# power_bus_v1.net
KiCad netlist of a schematic drawn in EAGLE
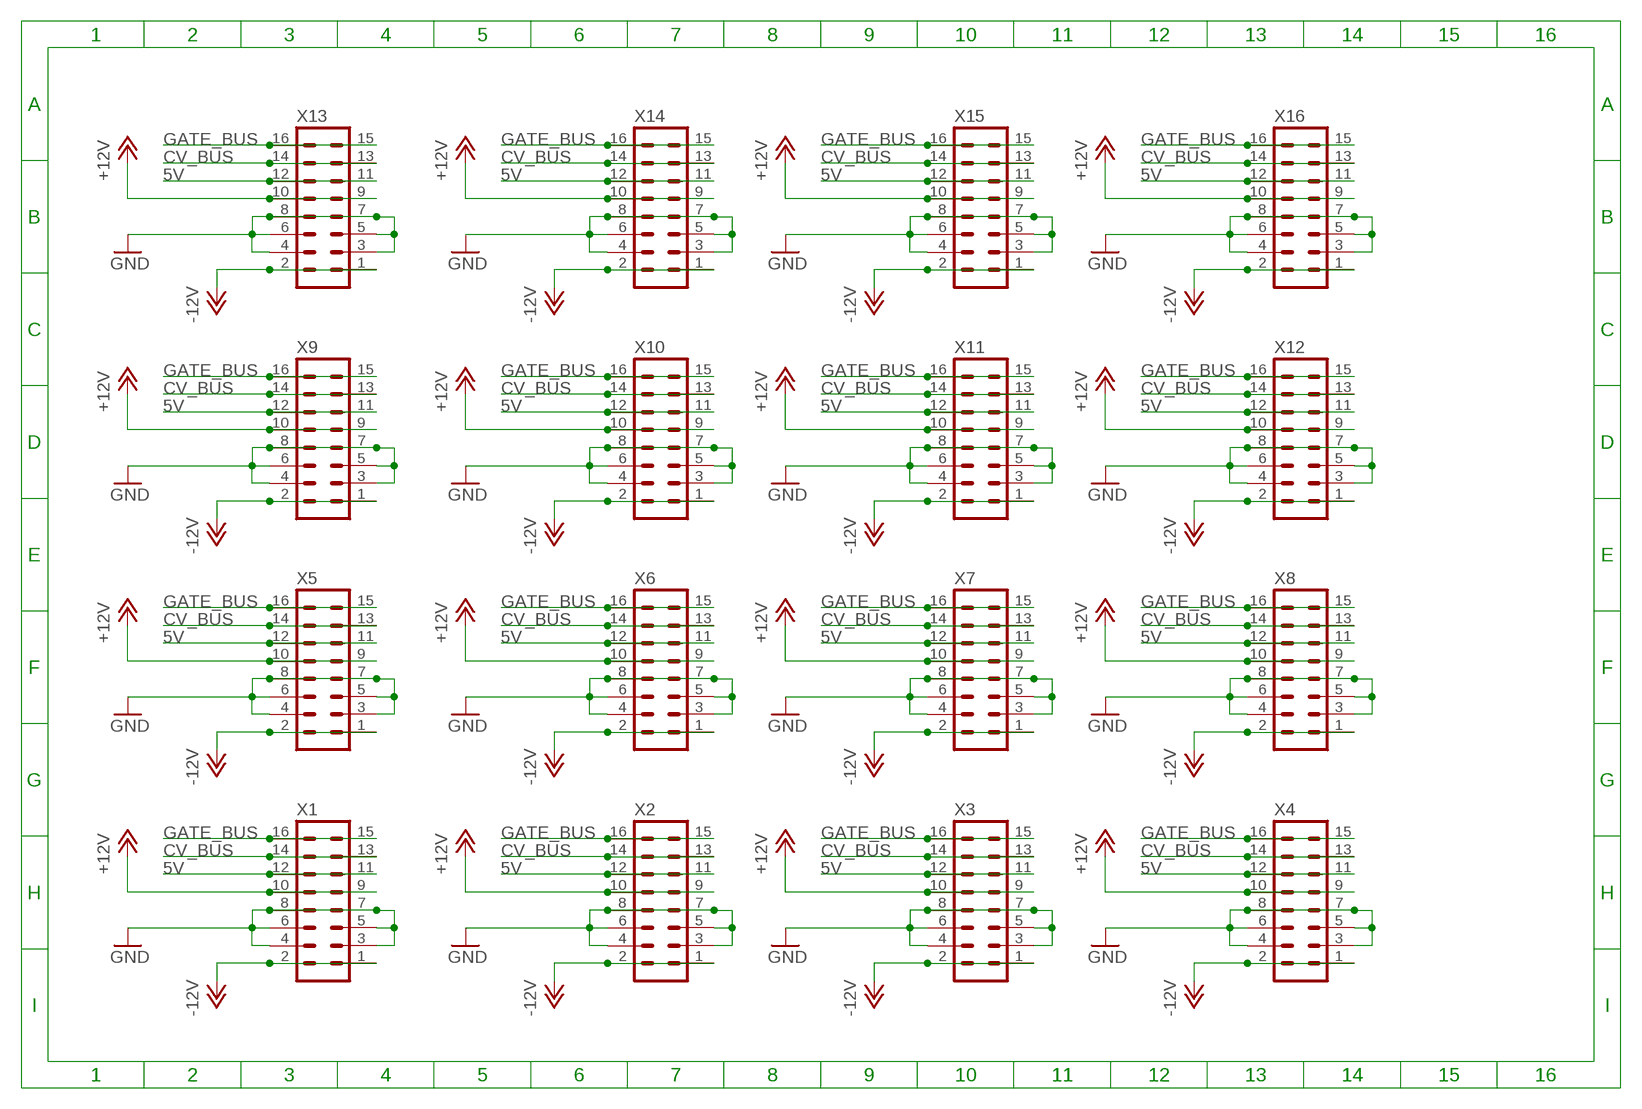
[diagram p0: schematic, sheet 1]

(export (version "E")
  (design (tool "Eeschema 10.0.6"))
  (components
    (comp (ref "X1")
      (value "ML16")
      (footprint "eagle-import:ML16")
      (libsource (lib "eagle-import") (part "ML16"))
    )
    (comp (ref "X2")
      (value "ML16")
      (footprint "eagle-import:ML16")
      (libsource (lib "eagle-import") (part "ML16"))
    )
    (comp (ref "X3")
      (value "ML16")
      (footprint "eagle-import:ML16")
      (libsource (lib "eagle-import") (part "ML16"))
    )
    (comp (ref "X4")
      (value "ML16")
      (footprint "eagle-import:ML16")
      (libsource (lib "eagle-import") (part "ML16"))
    )
    (comp (ref "X5")
      (value "ML16")
      (footprint "eagle-import:ML16")
      (libsource (lib "eagle-import") (part "ML16"))
    )
    (comp (ref "X6")
      (value "ML16")
      (footprint "eagle-import:ML16")
      (libsource (lib "eagle-import") (part "ML16"))
    )
    (comp (ref "X7")
      (value "ML16")
      (footprint "eagle-import:ML16")
      (libsource (lib "eagle-import") (part "ML16"))
    )
    (comp (ref "X8")
      (value "ML16")
      (footprint "eagle-import:ML16")
      (libsource (lib "eagle-import") (part "ML16"))
    )
    (comp (ref "X9")
      (value "ML16")
      (footprint "eagle-import:ML16")
      (libsource (lib "eagle-import") (part "ML16"))
    )
    (comp (ref "X10")
      (value "ML16")
      (footprint "eagle-import:ML16")
      (libsource (lib "eagle-import") (part "ML16"))
    )
    (comp (ref "X11")
      (value "ML16")
      (footprint "eagle-import:ML16")
      (libsource (lib "eagle-import") (part "ML16"))
    )
    (comp (ref "X12")
      (value "ML16")
      (footprint "eagle-import:ML16")
      (libsource (lib "eagle-import") (part "ML16"))
    )
    (comp (ref "X13")
      (value "ML16")
      (footprint "eagle-import:ML16")
      (libsource (lib "eagle-import") (part "ML16"))
    )
    (comp (ref "X14")
      (value "ML16")
      (footprint "eagle-import:ML16")
      (libsource (lib "eagle-import") (part "ML16"))
    )
    (comp (ref "X15")
      (value "ML16")
      (footprint "eagle-import:ML16")
      (libsource (lib "eagle-import") (part "ML16"))
    )
    (comp (ref "X16")
      (value "ML16")
      (footprint "eagle-import:ML16")
      (libsource (lib "eagle-import") (part "ML16"))
    )
  )
  (nets
    (net (code "1") (name "+12V") (class "Default")
      (node (ref "X1") (pin "10") (pinfunction "10_10") (pintype "passive"))
      (node (ref "X1") (pin "9") (pinfunction "9_9") (pintype "passive"))
      (node (ref "X10") (pin "10") (pinfunction "10_10") (pintype "passive"))
      (node (ref "X10") (pin "9") (pinfunction "9_9") (pintype "passive"))
      (node (ref "X11") (pin "10") (pinfunction "10_10") (pintype "passive"))
      (node (ref "X11") (pin "9") (pinfunction "9_9") (pintype "passive"))
      (node (ref "X12") (pin "10") (pinfunction "10_10") (pintype "passive"))
      (node (ref "X12") (pin "9") (pinfunction "9_9") (pintype "passive"))
      (node (ref "X13") (pin "10") (pinfunction "10_10") (pintype "passive"))
      (node (ref "X13") (pin "9") (pinfunction "9_9") (pintype "passive"))
      (node (ref "X14") (pin "10") (pinfunction "10_10") (pintype "passive"))
      (node (ref "X14") (pin "9") (pinfunction "9_9") (pintype "passive"))
      (node (ref "X15") (pin "10") (pinfunction "10_10") (pintype "passive"))
      (node (ref "X15") (pin "9") (pinfunction "9_9") (pintype "passive"))
      (node (ref "X16") (pin "10") (pinfunction "10_10") (pintype "passive"))
      (node (ref "X16") (pin "9") (pinfunction "9_9") (pintype "passive"))
      (node (ref "X2") (pin "10") (pinfunction "10_10") (pintype "passive"))
      (node (ref "X2") (pin "9") (pinfunction "9_9") (pintype "passive"))
      (node (ref "X3") (pin "10") (pinfunction "10_10") (pintype "passive"))
      (node (ref "X3") (pin "9") (pinfunction "9_9") (pintype "passive"))
      (node (ref "X4") (pin "10") (pinfunction "10_10") (pintype "passive"))
      (node (ref "X4") (pin "9") (pinfunction "9_9") (pintype "passive"))
      (node (ref "X5") (pin "10") (pinfunction "10_10") (pintype "passive"))
      (node (ref "X5") (pin "9") (pinfunction "9_9") (pintype "passive"))
      (node (ref "X6") (pin "10") (pinfunction "10_10") (pintype "passive"))
      (node (ref "X6") (pin "9") (pinfunction "9_9") (pintype "passive"))
      (node (ref "X7") (pin "10") (pinfunction "10_10") (pintype "passive"))
      (node (ref "X7") (pin "9") (pinfunction "9_9") (pintype "passive"))
      (node (ref "X8") (pin "10") (pinfunction "10_10") (pintype "passive"))
      (node (ref "X8") (pin "9") (pinfunction "9_9") (pintype "passive"))
      (node (ref "X9") (pin "10") (pinfunction "10_10") (pintype "passive"))
      (node (ref "X9") (pin "9") (pinfunction "9_9") (pintype "passive"))
    )
    (net (code "2") (name "-12V") (class "Default")
      (node (ref "X1") (pin "1") (pinfunction "1_1") (pintype "passive"))
      (node (ref "X1") (pin "2") (pinfunction "2_2") (pintype "passive"))
      (node (ref "X10") (pin "1") (pinfunction "1_1") (pintype "passive"))
      (node (ref "X10") (pin "2") (pinfunction "2_2") (pintype "passive"))
      (node (ref "X11") (pin "1") (pinfunction "1_1") (pintype "passive"))
      (node (ref "X11") (pin "2") (pinfunction "2_2") (pintype "passive"))
      (node (ref "X12") (pin "1") (pinfunction "1_1") (pintype "passive"))
      (node (ref "X12") (pin "2") (pinfunction "2_2") (pintype "passive"))
      (node (ref "X13") (pin "1") (pinfunction "1_1") (pintype "passive"))
      (node (ref "X13") (pin "2") (pinfunction "2_2") (pintype "passive"))
      (node (ref "X14") (pin "1") (pinfunction "1_1") (pintype "passive"))
      (node (ref "X14") (pin "2") (pinfunction "2_2") (pintype "passive"))
      (node (ref "X15") (pin "1") (pinfunction "1_1") (pintype "passive"))
      (node (ref "X15") (pin "2") (pinfunction "2_2") (pintype "passive"))
      (node (ref "X16") (pin "1") (pinfunction "1_1") (pintype "passive"))
      (node (ref "X16") (pin "2") (pinfunction "2_2") (pintype "passive"))
      (node (ref "X2") (pin "1") (pinfunction "1_1") (pintype "passive"))
      (node (ref "X2") (pin "2") (pinfunction "2_2") (pintype "passive"))
      (node (ref "X3") (pin "1") (pinfunction "1_1") (pintype "passive"))
      (node (ref "X3") (pin "2") (pinfunction "2_2") (pintype "passive"))
      (node (ref "X4") (pin "1") (pinfunction "1_1") (pintype "passive"))
      (node (ref "X4") (pin "2") (pinfunction "2_2") (pintype "passive"))
      (node (ref "X5") (pin "1") (pinfunction "1_1") (pintype "passive"))
      (node (ref "X5") (pin "2") (pinfunction "2_2") (pintype "passive"))
      (node (ref "X6") (pin "1") (pinfunction "1_1") (pintype "passive"))
      (node (ref "X6") (pin "2") (pinfunction "2_2") (pintype "passive"))
      (node (ref "X7") (pin "1") (pinfunction "1_1") (pintype "passive"))
      (node (ref "X7") (pin "2") (pinfunction "2_2") (pintype "passive"))
      (node (ref "X8") (pin "1") (pinfunction "1_1") (pintype "passive"))
      (node (ref "X8") (pin "2") (pinfunction "2_2") (pintype "passive"))
      (node (ref "X9") (pin "1") (pinfunction "1_1") (pintype "passive"))
      (node (ref "X9") (pin "2") (pinfunction "2_2") (pintype "passive"))
    )
    (net (code "3") (name "/5V") (class "Default")
      (node (ref "X1") (pin "11") (pinfunction "11_11") (pintype "passive"))
      (node (ref "X1") (pin "12") (pinfunction "12_12") (pintype "passive"))
      (node (ref "X10") (pin "11") (pinfunction "11_11") (pintype "passive"))
      (node (ref "X10") (pin "12") (pinfunction "12_12") (pintype "passive"))
      (node (ref "X11") (pin "11") (pinfunction "11_11") (pintype "passive"))
      (node (ref "X11") (pin "12") (pinfunction "12_12") (pintype "passive"))
      (node (ref "X12") (pin "11") (pinfunction "11_11") (pintype "passive"))
      (node (ref "X12") (pin "12") (pinfunction "12_12") (pintype "passive"))
      (node (ref "X13") (pin "11") (pinfunction "11_11") (pintype "passive"))
      (node (ref "X13") (pin "12") (pinfunction "12_12") (pintype "passive"))
      (node (ref "X14") (pin "11") (pinfunction "11_11") (pintype "passive"))
      (node (ref "X14") (pin "12") (pinfunction "12_12") (pintype "passive"))
      (node (ref "X15") (pin "11") (pinfunction "11_11") (pintype "passive"))
      (node (ref "X15") (pin "12") (pinfunction "12_12") (pintype "passive"))
      (node (ref "X16") (pin "11") (pinfunction "11_11") (pintype "passive"))
      (node (ref "X16") (pin "12") (pinfunction "12_12") (pintype "passive"))
      (node (ref "X2") (pin "11") (pinfunction "11_11") (pintype "passive"))
      (node (ref "X2") (pin "12") (pinfunction "12_12") (pintype "passive"))
      (node (ref "X3") (pin "11") (pinfunction "11_11") (pintype "passive"))
      (node (ref "X3") (pin "12") (pinfunction "12_12") (pintype "passive"))
      (node (ref "X4") (pin "11") (pinfunction "11_11") (pintype "passive"))
      (node (ref "X4") (pin "12") (pinfunction "12_12") (pintype "passive"))
      (node (ref "X5") (pin "11") (pinfunction "11_11") (pintype "passive"))
      (node (ref "X5") (pin "12") (pinfunction "12_12") (pintype "passive"))
      (node (ref "X6") (pin "11") (pinfunction "11_11") (pintype "passive"))
      (node (ref "X6") (pin "12") (pinfunction "12_12") (pintype "passive"))
      (node (ref "X7") (pin "11") (pinfunction "11_11") (pintype "passive"))
      (node (ref "X7") (pin "12") (pinfunction "12_12") (pintype "passive"))
      (node (ref "X8") (pin "11") (pinfunction "11_11") (pintype "passive"))
      (node (ref "X8") (pin "12") (pinfunction "12_12") (pintype "passive"))
      (node (ref "X9") (pin "11") (pinfunction "11_11") (pintype "passive"))
      (node (ref "X9") (pin "12") (pinfunction "12_12") (pintype "passive"))
    )
    (net (code "4") (name "/CV_BUS") (class "Default")
      (node (ref "X1") (pin "13") (pinfunction "13_13") (pintype "passive"))
      (node (ref "X1") (pin "14") (pinfunction "14_14") (pintype "passive"))
      (node (ref "X10") (pin "13") (pinfunction "13_13") (pintype "passive"))
      (node (ref "X10") (pin "14") (pinfunction "14_14") (pintype "passive"))
      (node (ref "X11") (pin "13") (pinfunction "13_13") (pintype "passive"))
      (node (ref "X11") (pin "14") (pinfunction "14_14") (pintype "passive"))
      (node (ref "X12") (pin "13") (pinfunction "13_13") (pintype "passive"))
      (node (ref "X12") (pin "14") (pinfunction "14_14") (pintype "passive"))
      (node (ref "X13") (pin "13") (pinfunction "13_13") (pintype "passive"))
      (node (ref "X13") (pin "14") (pinfunction "14_14") (pintype "passive"))
      (node (ref "X14") (pin "13") (pinfunction "13_13") (pintype "passive"))
      (node (ref "X14") (pin "14") (pinfunction "14_14") (pintype "passive"))
      (node (ref "X15") (pin "13") (pinfunction "13_13") (pintype "passive"))
      (node (ref "X15") (pin "14") (pinfunction "14_14") (pintype "passive"))
      (node (ref "X16") (pin "13") (pinfunction "13_13") (pintype "passive"))
      (node (ref "X16") (pin "14") (pinfunction "14_14") (pintype "passive"))
      (node (ref "X2") (pin "13") (pinfunction "13_13") (pintype "passive"))
      (node (ref "X2") (pin "14") (pinfunction "14_14") (pintype "passive"))
      (node (ref "X3") (pin "13") (pinfunction "13_13") (pintype "passive"))
      (node (ref "X3") (pin "14") (pinfunction "14_14") (pintype "passive"))
      (node (ref "X4") (pin "13") (pinfunction "13_13") (pintype "passive"))
      (node (ref "X4") (pin "14") (pinfunction "14_14") (pintype "passive"))
      (node (ref "X5") (pin "13") (pinfunction "13_13") (pintype "passive"))
      (node (ref "X5") (pin "14") (pinfunction "14_14") (pintype "passive"))
      (node (ref "X6") (pin "13") (pinfunction "13_13") (pintype "passive"))
      (node (ref "X6") (pin "14") (pinfunction "14_14") (pintype "passive"))
      (node (ref "X7") (pin "13") (pinfunction "13_13") (pintype "passive"))
      (node (ref "X7") (pin "14") (pinfunction "14_14") (pintype "passive"))
      (node (ref "X8") (pin "13") (pinfunction "13_13") (pintype "passive"))
      (node (ref "X8") (pin "14") (pinfunction "14_14") (pintype "passive"))
      (node (ref "X9") (pin "13") (pinfunction "13_13") (pintype "passive"))
      (node (ref "X9") (pin "14") (pinfunction "14_14") (pintype "passive"))
    )
    (net (code "5") (name "/GATE_BUS") (class "Default")
      (node (ref "X1") (pin "15") (pinfunction "15_15") (pintype "passive"))
      (node (ref "X1") (pin "16") (pinfunction "16_16") (pintype "passive"))
      (node (ref "X10") (pin "15") (pinfunction "15_15") (pintype "passive"))
      (node (ref "X10") (pin "16") (pinfunction "16_16") (pintype "passive"))
      (node (ref "X11") (pin "15") (pinfunction "15_15") (pintype "passive"))
      (node (ref "X11") (pin "16") (pinfunction "16_16") (pintype "passive"))
      (node (ref "X12") (pin "15") (pinfunction "15_15") (pintype "passive"))
      (node (ref "X12") (pin "16") (pinfunction "16_16") (pintype "passive"))
      (node (ref "X13") (pin "15") (pinfunction "15_15") (pintype "passive"))
      (node (ref "X13") (pin "16") (pinfunction "16_16") (pintype "passive"))
      (node (ref "X14") (pin "15") (pinfunction "15_15") (pintype "passive"))
      (node (ref "X14") (pin "16") (pinfunction "16_16") (pintype "passive"))
      (node (ref "X15") (pin "15") (pinfunction "15_15") (pintype "passive"))
      (node (ref "X15") (pin "16") (pinfunction "16_16") (pintype "passive"))
      (node (ref "X16") (pin "15") (pinfunction "15_15") (pintype "passive"))
      (node (ref "X16") (pin "16") (pinfunction "16_16") (pintype "passive"))
      (node (ref "X2") (pin "15") (pinfunction "15_15") (pintype "passive"))
      (node (ref "X2") (pin "16") (pinfunction "16_16") (pintype "passive"))
      (node (ref "X3") (pin "15") (pinfunction "15_15") (pintype "passive"))
      (node (ref "X3") (pin "16") (pinfunction "16_16") (pintype "passive"))
      (node (ref "X4") (pin "15") (pinfunction "15_15") (pintype "passive"))
      (node (ref "X4") (pin "16") (pinfunction "16_16") (pintype "passive"))
      (node (ref "X5") (pin "15") (pinfunction "15_15") (pintype "passive"))
      (node (ref "X5") (pin "16") (pinfunction "16_16") (pintype "passive"))
      (node (ref "X6") (pin "15") (pinfunction "15_15") (pintype "passive"))
      (node (ref "X6") (pin "16") (pinfunction "16_16") (pintype "passive"))
      (node (ref "X7") (pin "15") (pinfunction "15_15") (pintype "passive"))
      (node (ref "X7") (pin "16") (pinfunction "16_16") (pintype "passive"))
      (node (ref "X8") (pin "15") (pinfunction "15_15") (pintype "passive"))
      (node (ref "X8") (pin "16") (pinfunction "16_16") (pintype "passive"))
      (node (ref "X9") (pin "15") (pinfunction "15_15") (pintype "passive"))
      (node (ref "X9") (pin "16") (pinfunction "16_16") (pintype "passive"))
    )
    (net (code "6") (name "GND") (class "Default")
      (node (ref "X1") (pin "3") (pinfunction "3_3") (pintype "passive"))
      (node (ref "X1") (pin "4") (pinfunction "4_4") (pintype "passive"))
      (node (ref "X1") (pin "5") (pinfunction "5_5") (pintype "passive"))
      (node (ref "X1") (pin "6") (pinfunction "6_6") (pintype "passive"))
      (node (ref "X1") (pin "7") (pinfunction "7_7") (pintype "passive"))
      (node (ref "X1") (pin "8") (pinfunction "8_8") (pintype "passive"))
      (node (ref "X10") (pin "3") (pinfunction "3_3") (pintype "passive"))
      (node (ref "X10") (pin "4") (pinfunction "4_4") (pintype "passive"))
      (node (ref "X10") (pin "5") (pinfunction "5_5") (pintype "passive"))
      (node (ref "X10") (pin "6") (pinfunction "6_6") (pintype "passive"))
      (node (ref "X10") (pin "7") (pinfunction "7_7") (pintype "passive"))
      (node (ref "X10") (pin "8") (pinfunction "8_8") (pintype "passive"))
      (node (ref "X11") (pin "3") (pinfunction "3_3") (pintype "passive"))
      (node (ref "X11") (pin "4") (pinfunction "4_4") (pintype "passive"))
      (node (ref "X11") (pin "5") (pinfunction "5_5") (pintype "passive"))
      (node (ref "X11") (pin "6") (pinfunction "6_6") (pintype "passive"))
      (node (ref "X11") (pin "7") (pinfunction "7_7") (pintype "passive"))
      (node (ref "X11") (pin "8") (pinfunction "8_8") (pintype "passive"))
      (node (ref "X12") (pin "3") (pinfunction "3_3") (pintype "passive"))
      (node (ref "X12") (pin "4") (pinfunction "4_4") (pintype "passive"))
      (node (ref "X12") (pin "5") (pinfunction "5_5") (pintype "passive"))
      (node (ref "X12") (pin "6") (pinfunction "6_6") (pintype "passive"))
      (node (ref "X12") (pin "7") (pinfunction "7_7") (pintype "passive"))
      (node (ref "X12") (pin "8") (pinfunction "8_8") (pintype "passive"))
      (node (ref "X13") (pin "3") (pinfunction "3_3") (pintype "passive"))
      (node (ref "X13") (pin "4") (pinfunction "4_4") (pintype "passive"))
      (node (ref "X13") (pin "5") (pinfunction "5_5") (pintype "passive"))
      (node (ref "X13") (pin "6") (pinfunction "6_6") (pintype "passive"))
      (node (ref "X13") (pin "7") (pinfunction "7_7") (pintype "passive"))
      (node (ref "X13") (pin "8") (pinfunction "8_8") (pintype "passive"))
      (node (ref "X14") (pin "3") (pinfunction "3_3") (pintype "passive"))
      (node (ref "X14") (pin "4") (pinfunction "4_4") (pintype "passive"))
      (node (ref "X14") (pin "5") (pinfunction "5_5") (pintype "passive"))
      (node (ref "X14") (pin "6") (pinfunction "6_6") (pintype "passive"))
      (node (ref "X14") (pin "7") (pinfunction "7_7") (pintype "passive"))
      (node (ref "X14") (pin "8") (pinfunction "8_8") (pintype "passive"))
      (node (ref "X15") (pin "3") (pinfunction "3_3") (pintype "passive"))
      (node (ref "X15") (pin "4") (pinfunction "4_4") (pintype "passive"))
      (node (ref "X15") (pin "5") (pinfunction "5_5") (pintype "passive"))
      (node (ref "X15") (pin "6") (pinfunction "6_6") (pintype "passive"))
      (node (ref "X15") (pin "7") (pinfunction "7_7") (pintype "passive"))
      (node (ref "X15") (pin "8") (pinfunction "8_8") (pintype "passive"))
      (node (ref "X16") (pin "3") (pinfunction "3_3") (pintype "passive"))
      (node (ref "X16") (pin "4") (pinfunction "4_4") (pintype "passive"))
      (node (ref "X16") (pin "5") (pinfunction "5_5") (pintype "passive"))
      (node (ref "X16") (pin "6") (pinfunction "6_6") (pintype "passive"))
      (node (ref "X16") (pin "7") (pinfunction "7_7") (pintype "passive"))
      (node (ref "X16") (pin "8") (pinfunction "8_8") (pintype "passive"))
      (node (ref "X2") (pin "3") (pinfunction "3_3") (pintype "passive"))
      (node (ref "X2") (pin "4") (pinfunction "4_4") (pintype "passive"))
      (node (ref "X2") (pin "5") (pinfunction "5_5") (pintype "passive"))
      (node (ref "X2") (pin "6") (pinfunction "6_6") (pintype "passive"))
      (node (ref "X2") (pin "7") (pinfunction "7_7") (pintype "passive"))
      (node (ref "X2") (pin "8") (pinfunction "8_8") (pintype "passive"))
      (node (ref "X3") (pin "3") (pinfunction "3_3") (pintype "passive"))
      (node (ref "X3") (pin "4") (pinfunction "4_4") (pintype "passive"))
      (node (ref "X3") (pin "5") (pinfunction "5_5") (pintype "passive"))
      (node (ref "X3") (pin "6") (pinfunction "6_6") (pintype "passive"))
      (node (ref "X3") (pin "7") (pinfunction "7_7") (pintype "passive"))
      (node (ref "X3") (pin "8") (pinfunction "8_8") (pintype "passive"))
      (node (ref "X4") (pin "3") (pinfunction "3_3") (pintype "passive"))
      (node (ref "X4") (pin "4") (pinfunction "4_4") (pintype "passive"))
      (node (ref "X4") (pin "5") (pinfunction "5_5") (pintype "passive"))
      (node (ref "X4") (pin "6") (pinfunction "6_6") (pintype "passive"))
      (node (ref "X4") (pin "7") (pinfunction "7_7") (pintype "passive"))
      (node (ref "X4") (pin "8") (pinfunction "8_8") (pintype "passive"))
      (node (ref "X5") (pin "3") (pinfunction "3_3") (pintype "passive"))
      (node (ref "X5") (pin "4") (pinfunction "4_4") (pintype "passive"))
      (node (ref "X5") (pin "5") (pinfunction "5_5") (pintype "passive"))
      (node (ref "X5") (pin "6") (pinfunction "6_6") (pintype "passive"))
      (node (ref "X5") (pin "7") (pinfunction "7_7") (pintype "passive"))
      (node (ref "X5") (pin "8") (pinfunction "8_8") (pintype "passive"))
      (node (ref "X6") (pin "3") (pinfunction "3_3") (pintype "passive"))
      (node (ref "X6") (pin "4") (pinfunction "4_4") (pintype "passive"))
      (node (ref "X6") (pin "5") (pinfunction "5_5") (pintype "passive"))
      (node (ref "X6") (pin "6") (pinfunction "6_6") (pintype "passive"))
      (node (ref "X6") (pin "7") (pinfunction "7_7") (pintype "passive"))
      (node (ref "X6") (pin "8") (pinfunction "8_8") (pintype "passive"))
      (node (ref "X7") (pin "3") (pinfunction "3_3") (pintype "passive"))
      (node (ref "X7") (pin "4") (pinfunction "4_4") (pintype "passive"))
      (node (ref "X7") (pin "5") (pinfunction "5_5") (pintype "passive"))
      (node (ref "X7") (pin "6") (pinfunction "6_6") (pintype "passive"))
      (node (ref "X7") (pin "7") (pinfunction "7_7") (pintype "passive"))
      (node (ref "X7") (pin "8") (pinfunction "8_8") (pintype "passive"))
      (node (ref "X8") (pin "3") (pinfunction "3_3") (pintype "passive"))
      (node (ref "X8") (pin "4") (pinfunction "4_4") (pintype "passive"))
      (node (ref "X8") (pin "5") (pinfunction "5_5") (pintype "passive"))
      (node (ref "X8") (pin "6") (pinfunction "6_6") (pintype "passive"))
      (node (ref "X8") (pin "7") (pinfunction "7_7") (pintype "passive"))
      (node (ref "X8") (pin "8") (pinfunction "8_8") (pintype "passive"))
      (node (ref "X9") (pin "3") (pinfunction "3_3") (pintype "passive"))
      (node (ref "X9") (pin "4") (pinfunction "4_4") (pintype "passive"))
      (node (ref "X9") (pin "5") (pinfunction "5_5") (pintype "passive"))
      (node (ref "X9") (pin "6") (pinfunction "6_6") (pintype "passive"))
      (node (ref "X9") (pin "7") (pinfunction "7_7") (pintype "passive"))
      (node (ref "X9") (pin "8") (pinfunction "8_8") (pintype "passive"))
    )
  )
)
